# Communication.net
KiCad netlist of a schematic drawn in Altium Designer
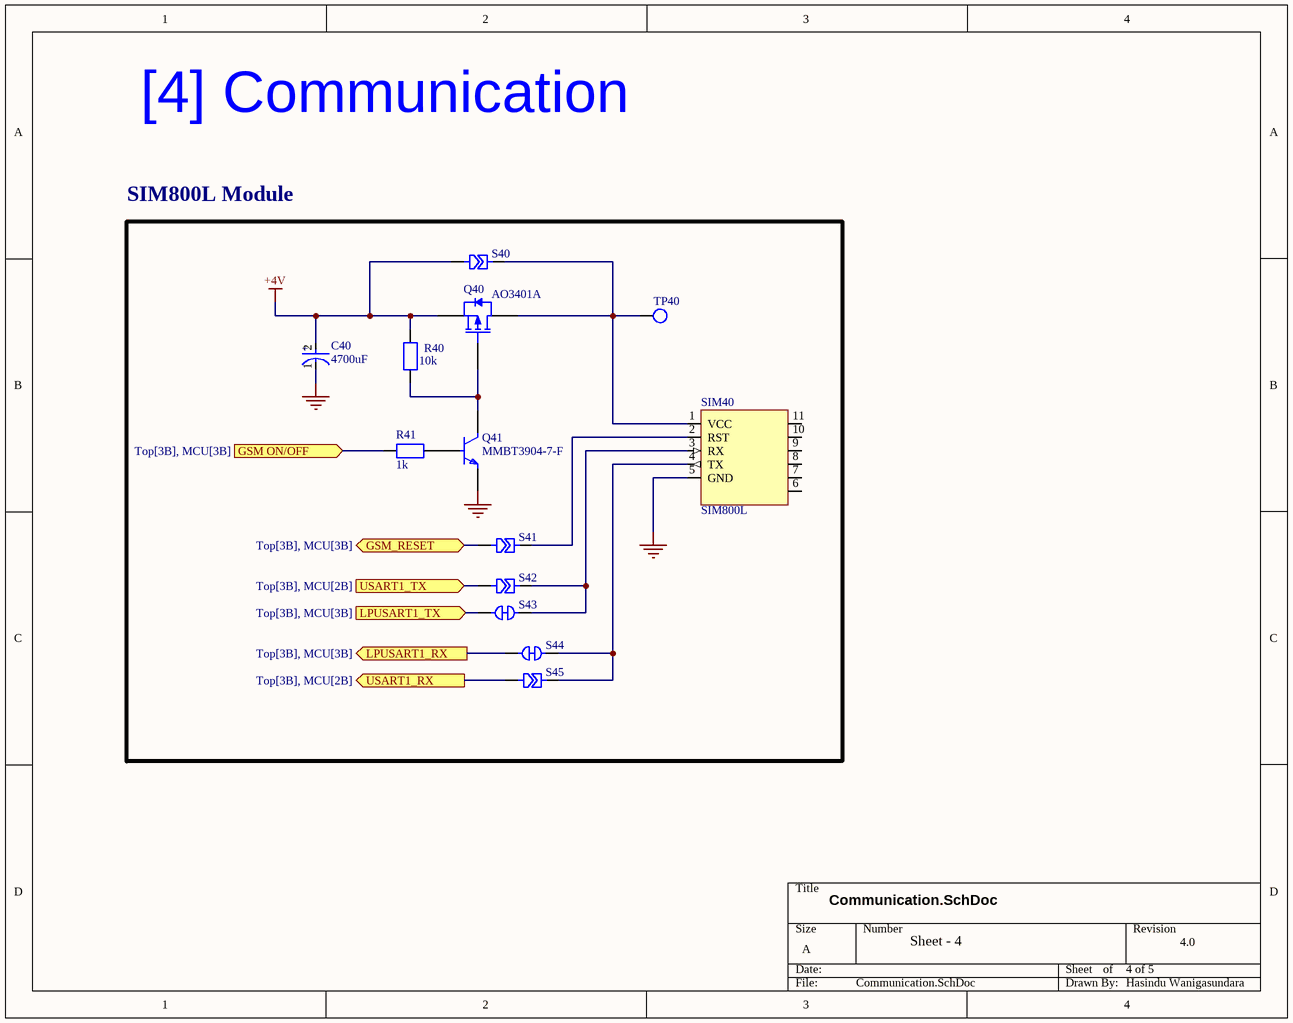
[diagram p0: Communication.SchDoc]

(export (version "E")
  (design (tool "Eeschema 10.0.6"))
  (components
    (comp (ref "C40")
      (value "4700uF")
      (footprint "FP-RAD-TH-D_12_5_0_5-L_30-MFG")
      (description "Aluminum Electrolytic Capacitors (Radial Lead Type) AEC-Q200 Qualified 4700uF ±20% 10V")
      (libsource (lib "Altium Content Vault") (part "203bc49f2ac43e59fd269a8c329ed05"))
    )
    (comp (ref "Q40")
      (value "AO3401A")
      (footprint "AO-SOT-23-3L_V")
      (description "P-Channel MOSFET, 30 V, 4 A, -55 to 150 degC, 3-Pin SOT-23-3L, RoHS, Tape and Reel")
      (fields (field (name "MANUFACTURER") "Alpha and Omega"))
      (libsource (lib "Altium Content Vault") (part "PEMOS-GSD-3"))
    )
    (comp (ref "Q41")
      (value "MMBT3904-7-F")
      (footprint "FP-SOT23-IPC_A")
      (description "TRANS NPN 40V 0.2A SMD SOT23-3")
      (libsource (lib "Altium Content Vault") (part "b44e953556f554d0102664c7d152cb4"))
    )
    (comp (ref "R40")
      (value "10k")
      (footprint "RES_1206")
      (description "SMD 3.2mm × 1.6mm size resistor (1206)")
      (libsource (lib "EDR - Water Meter") (part "RES_1206"))
    )
    (comp (ref "R41")
      (value "1k")
      (footprint "RES_1206")
      (description "SMD 3.2mm × 1.6mm size resistor (1206)")
      (libsource (lib "EDR - Water Meter") (part "RES_1206"))
    )
    (comp (ref "S40")
      (value "Triangular SB")
      (footprint "Solder Bridge Triangular")
      (description "Solder Bridge triangular closed")
      (libsource (lib "EDR - Water Meter") (part "Triangular SB"))
    )
    (comp (ref "S41")
      (value "Triangular SB")
      (footprint "Solder Bridge Triangular")
      (description "Solder Bridge triangular closed")
      (libsource (lib "EDR - Water Meter") (part "Triangular SB"))
    )
    (comp (ref "S42")
      (value "Triangular SB")
      (footprint "Solder Bridge Triangular")
      (description "Solder Bridge triangular closed")
      (libsource (lib "EDR - Water Meter") (part "Triangular SB"))
    )
    (comp (ref "S43")
      (value "Soldering Bridge close")
      (footprint "Circular jumper close")
      (description "Soldering Bridge close SMD")
      (libsource (lib "EDR - Water Meter") (part "Soldering Bridge close"))
    )
    (comp (ref "S44")
      (value "Soldering Bridge close")
      (footprint "Circular jumper close")
      (description "Soldering Bridge close SMD")
      (libsource (lib "EDR - Water Meter") (part "Soldering Bridge close"))
    )
    (comp (ref "S45")
      (value "Triangular SB")
      (footprint "Solder Bridge Triangular")
      (description "Solder Bridge triangular closed")
      (libsource (lib "EDR - Water Meter") (part "Triangular SB"))
    )
    (comp (ref "SIM40")
      (value "SIM800L")
      (footprint "SIM800L")
      (description "SIM800L through hole gsm module")
      (libsource (lib "EDR - Water Meter") (part "SIM800L"))
    )
    (comp (ref "TP40")
      (value "Test Pad")
      (footprint "Test Pad")
      (libsource (lib "EDR - Water Meter") (part "Test Pad"))
    )
  )
  (nets
    (net (code "1") (name "+4V") (class "Default")
      (node (ref "C40") (pin "2") (pinfunction "A_2") (pintype "passive"))
      (node (ref "Q40") (pin "2") (pinfunction "SOURCE_2") (pintype "passive"))
      (node (ref "R40") (pin "1") (pintype "passive"))
      (node (ref "S40") (pin "1") (pintype "passive"))
    )
    (net (code "2") (name "/GSM ON{slash}OFF") (class "Default")
      (node (ref "R41") (pin "1") (pintype "passive"))
    )
    (net (code "3") (name "/GSM_RESET") (class "Default") (node (ref "S41") (pin "1") (pintype "passive")))
    (net (code "4") (name "/LPUSART1_RX") (class "Default") (node (ref "S44") (pin "1") (pintype "passive")))
    (net (code "5") (name "/LPUSART1_TX") (class "Default") (node (ref "S43") (pin "1") (pintype "passive")))
    (net (code "6") (name "/USART1_RX") (class "Default") (node (ref "S45") (pin "1") (pintype "passive")))
    (net (code "7") (name "/USART1_TX") (class "Default") (node (ref "S42") (pin "1") (pintype "passive")))
    (net (code "8") (name "GND") (class "Default")
      (node (ref "C40") (pin "1") (pinfunction "C_1") (pintype "passive"))
      (node (ref "Q41") (pin "2") (pinfunction "E_2") (pintype "passive"))
      (node (ref "SIM40") (pin "5") (pinfunction "GND_5") (pintype "passive"))
    )
    (net (code "9") (name "Net-(Q40-DRAIN)") (class "Default")
      (node (ref "Q40") (pin "3") (pinfunction "DRAIN_3") (pintype "passive"))
      (node (ref "S40") (pin "2") (pintype "passive"))
      (node (ref "SIM40") (pin "1") (pinfunction "VCC_1") (pintype "power_in"))
      (node (ref "TP40") (pin "1") (pintype "passive"))
    )
    (net (code "10") (name "Net-(Q40-GATE)") (class "Default")
      (node (ref "Q40") (pin "1") (pinfunction "GATE_1") (pintype "passive"))
      (node (ref "Q41") (pin "3") (pinfunction "C_3") (pintype "passive"))
      (node (ref "R40") (pin "2") (pintype "passive"))
    )
    (net (code "11") (name "Net-(Q41-B)") (class "Default")
      (node (ref "Q41") (pin "1") (pinfunction "B_1") (pintype "passive"))
      (node (ref "R41") (pin "2") (pintype "passive"))
    )
    (net (code "12") (name "Net-(SIM40-RST)") (class "Default")
      (node (ref "S41") (pin "2") (pintype "passive"))
      (node (ref "SIM40") (pin "2") (pinfunction "RST_2") (pintype "passive"))
    )
    (net (code "13") (name "Net-(SIM40-RX)") (class "Default")
      (node (ref "S42") (pin "2") (pintype "passive"))
      (node (ref "S43") (pin "2") (pintype "passive"))
      (node (ref "SIM40") (pin "3") (pinfunction "RX_3") (pintype "input"))
    )
    (net (code "14") (name "Net-(SIM40-TX)") (class "Default")
      (node (ref "S44") (pin "2") (pintype "passive"))
      (node (ref "S45") (pin "2") (pintype "passive"))
      (node (ref "SIM40") (pin "4") (pinfunction "TX_4") (pintype "output"))
    )
    (net (code "15") (name "unconnected-(SIM40-Pad6)") (class "Default")
      (node (ref "SIM40") (pin "6") (pintype "passive"))
    )
    (net (code "16") (name "unconnected-(SIM40-Pad7)") (class "Default")
      (node (ref "SIM40") (pin "7") (pintype "passive"))
    )
    (net (code "17") (name "unconnected-(SIM40-Pad8)") (class "Default")
      (node (ref "SIM40") (pin "8") (pintype "passive"))
    )
    (net (code "18") (name "unconnected-(SIM40-Pad9)") (class "Default")
      (node (ref "SIM40") (pin "9") (pintype "passive"))
    )
    (net (code "19") (name "unconnected-(SIM40-Pad10)") (class "Default")
      (node (ref "SIM40") (pin "10") (pintype "passive"))
    )
    (net (code "20") (name "unconnected-(SIM40-Pad11)") (class "Default")
      (node (ref "SIM40") (pin "11") (pintype "passive"))
    )
  )
)
